# Flyback_SMPS.net
KiCad netlist of a schematic drawn in Altium Designer
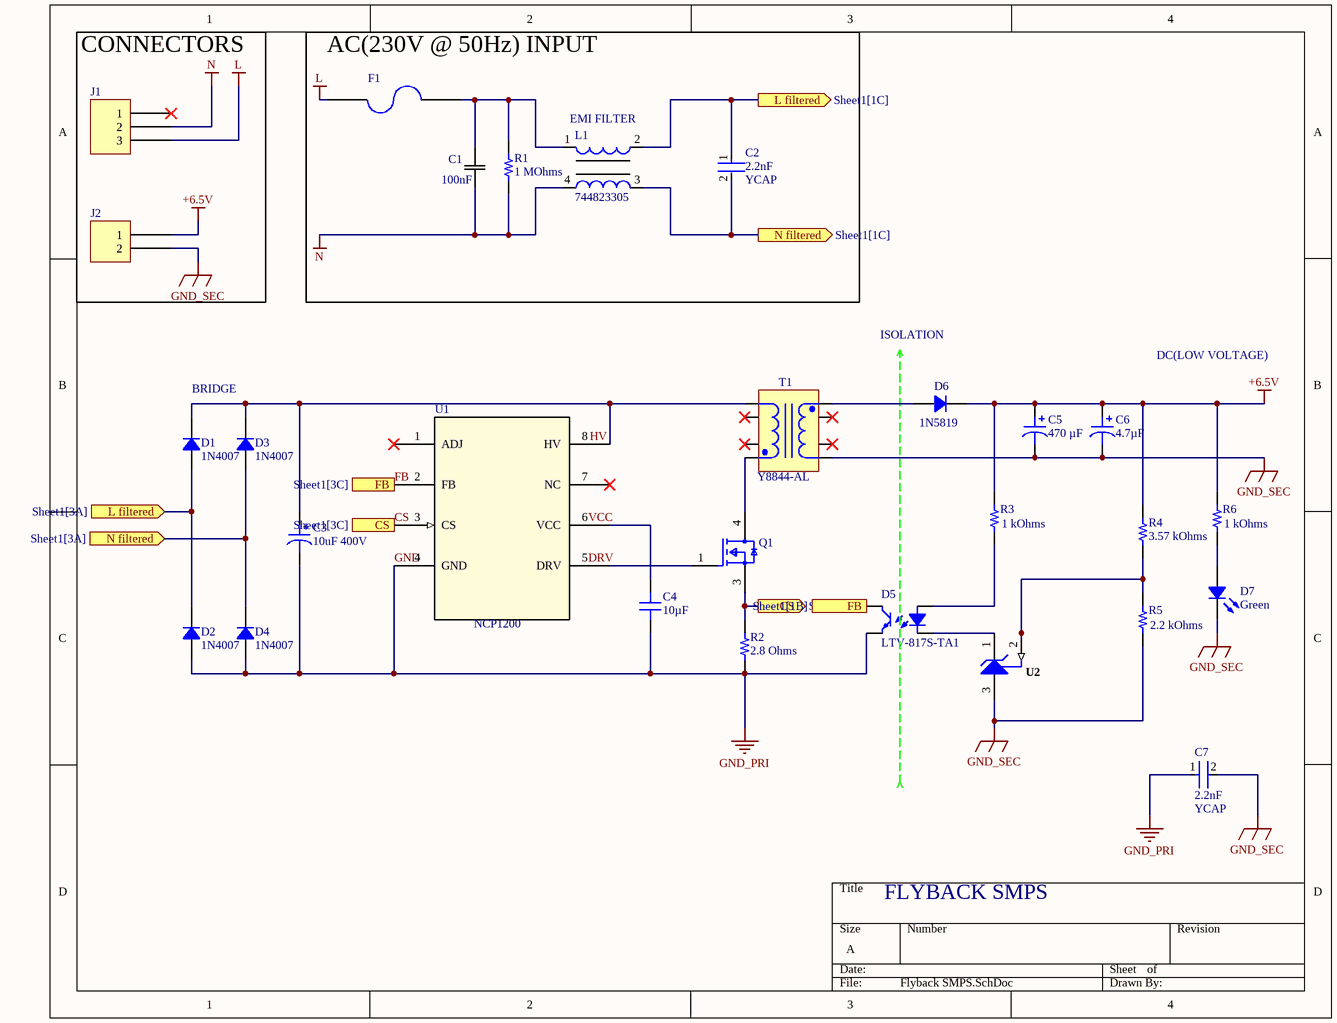
[diagram p0: Flyback SMPS.SchDoc]

(export (version "E")
  (design (tool "Eeschema 10.0.6"))
  (components
    (comp (ref "C1")
      (value "100nF")
      (footprint "CAP_B32652A--15--8.5x14.5x18_TDK")
      (description "No Description Available")
      (fields
        (field (name "MANUFACTURER_PART_NUMBER") "B32652A1103J000")
        (field (name "COPYRIGHT") "Copyright (C) 2025 Ultra Librarian. All rights reserved.")
      )
      (libsource (lib "transformer") (part "B32652A1103J000"))
    )
    (comp (ref "C2")
      (value "YCAP")
      (footprint "Vishay_0_MFG")
      (description "2200 pF ±20% 500VAC Ceramic Capacitor Y5V (F) Radial, Disc")
      (fields
        (field (name "TOLERANCE") "20%")
        (field (name "MANUFACTURER") "Vishay")
        (field (name "ALTIUM_VALUE") "2.2nF")
      )
      (libsource (lib "Tiberiu's Altium Workspace") (part "VY1222M37Y5VQ63V0"))
    )
    (comp (ref "C3")
      (value "10uF 400V")
      (footprint "CAP TH ALUM ELEC D10.00mm S5.00mm H17.50mm")
      (description "CAP 10 UF 20% 400 V")
      (fields (field (name "PART NUMBER") "860241375002") (field (name "MANUFACTURER") "Würth Elektronik"))
      (libsource (lib "Celestial Altium Library - altium_library") (part "Polarised Capacitor"))
    )
    (comp (ref "C4")
      (value "10µF")
      (footprint "CAP 1206_3216 - 1.8MM")
      (description "CAP CER 10UF 50V X5R 1206")
      (fields
        (field (name "PART NUMBER") "12065D106KAT2A")
        (field (name "CAPACITANCE") "10µF")
        (field (name "MANUFACTURER") "AVX Corporation")
      )
      (libsource (lib "Celestial Altium Library - altium_library") (part "Capacitor"))
    )
    (comp (ref "C5")
      (value "470 µF")
      (footprint "CAP AL TH D8 L3.5 H12.5")
      (description "CAP ALUM 470UF 20% 16V RADIAL")
      (fields (field (name "PART NUMBER") "UKW1C471MPD1TD") (field (name "MANUFACTURER") "Nichicon"))
      (libsource (lib "Celestial Altium Library - altium_library") (part "Polarised Capacitor"))
    )
    (comp (ref "C6")
      (value "4.7µF")
      (footprint "CAP TH ALUM ELEC D4.00mm S1.50mm H6.00mm")
      (description "CAP ALUM 4.7UF 20% 16V RADIAL")
      (fields (field (name "PART NUMBER") "UMP1C4R7MDD1TP") (field (name "MANUFACTURER") "Nichicon"))
      (libsource (lib "Celestial Altium Library - altium_library") (part "Polarised Capacitor"))
    )
    (comp (ref "C7")
      (value "YCAP")
      (footprint "Vishay_0_MFG")
      (description "2200 pF ±20% 500VAC Ceramic Capacitor Y5V (F) Radial, Disc")
      (fields
        (field (name "TOLERANCE") "20%")
        (field (name "MANUFACTURER") "Vishay")
        (field (name "ALTIUM_VALUE") "2.2nF")
      )
      (libsource (lib "Tiberiu's Altium Workspace") (part "VY1222M37Y5VQ63V0"))
    )
    (comp (ref "D1")
      (value "1N4007")
      (footprint "SOD123F")
      (description "STANDARD RECTIFIER 1000V SOD-123")
      (fields (field (name "PART NUMBER") "1N4007FLTR") (field (name "MANUFACTURER") "SMC Diode Solutions"))
      (libsource (lib "Celestial Altium Library - altium_library") (part "Diode"))
    )
    (comp (ref "D2")
      (value "1N4007")
      (footprint "SOD123F")
      (description "STANDARD RECTIFIER 1000V SOD-123")
      (fields (field (name "PART NUMBER") "1N4007FLTR") (field (name "MANUFACTURER") "SMC Diode Solutions"))
      (libsource (lib "Celestial Altium Library - altium_library") (part "Diode"))
    )
    (comp (ref "D3")
      (value "1N4007")
      (footprint "SOD123F")
      (description "STANDARD RECTIFIER 1000V SOD-123")
      (fields (field (name "PART NUMBER") "1N4007FLTR") (field (name "MANUFACTURER") "SMC Diode Solutions"))
      (libsource (lib "Celestial Altium Library - altium_library") (part "Diode"))
    )
    (comp (ref "D4")
      (value "1N4007")
      (footprint "SOD123F")
      (description "STANDARD RECTIFIER 1000V SOD-123")
      (fields (field (name "PART NUMBER") "1N4007FLTR") (field (name "MANUFACTURER") "SMC Diode Solutions"))
      (libsource (lib "Celestial Altium Library - altium_library") (part "Diode"))
    )
    (comp (ref "D5")
      (value "LTV-817S-TA1")
      (footprint "LITEON LTV-817")
      (description "OPTOISOLATR 5KV TRANSISTOR 4-SMD")
      (fields (field (name "MANUFACTURER") "Lite-On Inc."))
      (libsource (lib "Celestial Altium Library - altium_library") (part "Optoisolator"))
    )
    (comp (ref "D6")
      (value "1N5819")
      (footprint "SOD-123")
      (description "DIODE SCHOTTKY 40V 1A SOD123")
      (fields (field (name "PART NUMBER") "1N5819HW-7-F") (field (name "MANUFACTURER") "Diodes Incorporated"))
      (libsource (lib "Celestial Altium Library - altium_library") (part "Diode"))
    )
    (comp (ref "D7")
      (value "Green")
      (footprint "LED 0603_1608 GREEN")
      (description "NEXT GENERATION OF CHIP LED 0603")
      (fields
        (field (name "PART NUMBER") "LT Q99G.01-R2T1-25-1")
        (field (name "MANUFACTURER") "ams-OSRAM USA Inc.")
      )
      (libsource (lib "Celestial Altium Library - altium_library") (part "LED"))
    )
    (comp (ref "F1")
      (value "0679H2000-05")
      (footprint "FUSE 2410_6125 2")
      (description "FUSE BOARD MNT 2A 350VAC 72VDC")
      (fields (field (name "MANUFACTURER") "Bel Fuse Inc."))
      (libsource (lib "Celestial Altium Library - altium_library") (part "FUSE 0679H3500-05"))
    )
    (comp (ref "J1")
      (value "Part Number")
      (footprint "TE 282834-3")
      (description "TERM BLK 3P SIDE ENT 2.54MM PCB")
      (fields
        (field (name "PART NUMBER") "282834-3")
        (field (name "MANUFACTURER") "TE Connectivity AMP Connectors")
      )
      (libsource (lib "Celestial Altium Library - altium_library") (part "3 Pin"))
    )
    (comp (ref "J2")
      (value "282837-2")
      (footprint "TE 282837-2")
      (description "TERM BLK 2P SIDE ENT 5.08MM PCB")
      (fields (field (name "MANUFACTURER") "TE Connectivity AMP Connectors") (field (name "VOLTAGE") "300 V"))
      (libsource (lib "Celestial Altium Library - altium_library") (part "2 Pin"))
    )
    (comp (ref "L1")
      (value "744823305")
      (footprint "WE-CMB-M")
      (description "THT Common Mode Power Line Choke WE-CMB, L = 5.00 mH")
      (libsource (lib "transformer") (part "744823305"))
    )
    (comp (ref "Q1")
      (value "STD1NK60T4")
      (footprint "STMicroelectronics_DPAK_TO-252_-0068772_MFG")
      (description "N-Channel 600V 1A (Tc) 30W (Tc) Surface Mount DPAK")
      (fields
        (field (name "DIGIKEY PART NUMBER") "497-2483-1-ND")
        (field (name "MOUSER PART NUMBER") "511-STD1NK60")
      )
      (libsource (lib "Tiberiu's Altium Workspace") (part "STD1NK60T4"))
    )
    (comp (ref "R1")
      (value "1 MOhms")
      (footprint "RES 1210_3225")
      (description "RES 1M OHM 1% 3/4W 1210")
      (fields
        (field (name "PART NUMBER") "CRGP1210F1M0")
        (field (name "MANUFACTURER") "TE Connectivity Passive Product")
      )
      (libsource (lib "Celestial Altium Library - altium_library") (part "Resistor"))
    )
    (comp (ref "R2")
      (value "2.8 Ohms")
      (footprint "RES 1206_3216")
      (description "CPF 1206 2R8 0.1% 25PPM 1K RL")
      (fields
        (field (name "PART NUMBER") "CPF1206B2R8E1")
        (field (name "MANUFACTURER") "TE Connectivity Passive Product")
      )
      (libsource (lib "Celestial Altium Library - altium_library") (part "Resistor"))
    )
    (comp (ref "R3")
      (value "1 kOhms")
      (footprint "RES 0402_1005")
      (description "RES SMD 1K OHM 0.1% 1/16W 0402")
      (fields
        (field (name "PART NUMBER") "CPF0402B1K0E")
        (field (name "MANUFACTURER") "TE Connectivity Passive Product")
      )
      (libsource (lib "Celestial Altium Library - altium_library") (part "Resistor"))
    )
    (comp (ref "R4")
      (value "3.57 kOhms")
      (footprint "YAGEO RES 1206_3216")
      (description "RES 3.57K OHM 1% 1/16W 0402")
      (fields (field (name "PART NUMBER") "RC0402FR-073K57L") (field (name "MANUFACTURER") "Yageo"))
      (libsource (lib "Celestial Altium Library - altium_library") (part "Resistor"))
    )
    (comp (ref "R5")
      (value "2.2 kOhms")
      (footprint "RES 0402_1005")
      (description "RES SMD 2.2K OHM 0.5% 1/16W 0402")
      (fields (field (name "PART NUMBER") "RR0510P-222-D") (field (name "MANUFACTURER") "Susumu"))
      (libsource (lib "Celestial Altium Library - altium_library") (part "Resistor"))
    )
    (comp (ref "R6")
      (value "1 kOhms")
      (footprint "RES 0402_1005")
      (description "RES SMD 1K OHM 0.1% 1/16W 0402")
      (fields
        (field (name "PART NUMBER") "CPF0402B1K0E")
        (field (name "MANUFACTURER") "TE Connectivity Passive Product")
      )
      (libsource (lib "Celestial Altium Library - altium_library") (part "Resistor"))
    )
    (comp (ref "T1")
      (value "Y8844-AL")
      (footprint "COIL-Y8844-AL-8_V")
      (description "Flyback Transformer, 3.5 W, -40 to 85 degC, 18.3 x 20.1 x 14 mm Package")
      (fields (field (name "MANUFACTURER") "Coilcraft"))
      (libsource (lib "transformer") (part "Y8844-AL"))
    )
    (comp (ref "U1")
      (value "NCP1200")
      (footprint "SOIC8_ONS")
      (description "No Description Available")
      (fields
        (field (name "MANUFACTURER_PART_NUMBER") "NCP1200AD100R2")
        (field (name "COPYRIGHT") "Copyright (C) 2025 Ultra Librarian. All rights reserved.")
      )
      (libsource (lib "transformer") (part "NCP1200AD100R2"))
    )
    (comp (ref "U2")
      (value "TL431AQDBZRQ1")
      (footprint "DBZ0003A_L")
      (fields (field (name "MANUFACTURER") "Texas Instruments"))
      (libsource (lib "transformer") (part "TL431AQDBZRQ1"))
    )
  )
  (nets
    (net (code "1") (name "+6.5V") (class "Default")
      (node (ref "C5") (pin "1") (pinfunction "1_1") (pintype "passive"))
      (node (ref "C6") (pin "1") (pinfunction "1_1") (pintype "passive"))
      (node (ref "D6") (pin "2") (pinfunction "2_2") (pintype "passive"))
      (node (ref "J2") (pin "1") (pinfunction "1_1") (pintype "passive"))
      (node (ref "R3") (pin "2") (pinfunction "2_2") (pintype "passive"))
      (node (ref "R4") (pin "2") (pinfunction "2_2") (pintype "passive"))
      (node (ref "R6") (pin "2") (pinfunction "2_2") (pintype "passive"))
    )
    (net (code "2") (name "/CS") (class "Default")
      (node (ref "Q1") (pin "3") (pinfunction "S_3") (pintype "passive"))
      (node (ref "R2") (pin "2") (pinfunction "2_2") (pintype "passive"))
      (node (ref "U1") (pin "3") (pinfunction "CS_3") (pintype "input"))
    )
    (net (code "4") (name "/FB") (class "Default")
      (node (ref "D5") (pin "4") (pinfunction "4_4") (pintype "passive"))
      (node (ref "U1") (pin "2") (pinfunction "FB_2") (pintype "passive"))
    )
    (net (code "6") (name "/L filtered") (class "Default")
      (node (ref "C2") (pin "1") (pinfunction "1_1") (pintype "passive"))
      (node (ref "D1") (pin "1") (pinfunction "1_1") (pintype "passive"))
      (node (ref "D2") (pin "2") (pinfunction "2_2") (pintype "passive"))
      (node (ref "L1") (pin "2") (pinfunction "2_2") (pintype "passive"))
    )
    (net (code "7") (name "/N filtered") (class "Default")
      (node (ref "C2") (pin "2") (pinfunction "2_2") (pintype "passive"))
      (node (ref "D3") (pin "1") (pinfunction "1_1") (pintype "passive"))
      (node (ref "D4") (pin "2") (pinfunction "2_2") (pintype "passive"))
      (node (ref "L1") (pin "3") (pinfunction "3_3") (pintype "passive"))
    )
    (net (code "9") (name "GND_PRI") (class "Default")
      (node (ref "C3") (pin "2") (pinfunction "2_2") (pintype "passive"))
      (node (ref "C4") (pin "2") (pinfunction "2_2") (pintype "passive"))
      (node (ref "C7") (pin "1") (pinfunction "1_1") (pintype "passive"))
      (node (ref "D2") (pin "1") (pinfunction "1_1") (pintype "passive"))
      (node (ref "D4") (pin "1") (pinfunction "1_1") (pintype "passive"))
      (node (ref "D5") (pin "3") (pinfunction "3_3") (pintype "passive"))
      (node (ref "R2") (pin "1") (pinfunction "1_1") (pintype "passive"))
      (node (ref "U1") (pin "4") (pinfunction "GND_4") (pintype "power_in"))
    )
    (net (code "10") (name "GND_SEC") (class "Default")
      (node (ref "C5") (pin "2") (pinfunction "2_2") (pintype "passive"))
      (node (ref "C6") (pin "2") (pinfunction "2_2") (pintype "passive"))
      (node (ref "C7") (pin "2") (pinfunction "2_2") (pintype "passive"))
      (node (ref "D7") (pin "2") (pinfunction "2_2") (pintype "passive"))
      (node (ref "J2") (pin "2") (pinfunction "2_2") (pintype "passive"))
      (node (ref "R5") (pin "1") (pinfunction "1_1") (pintype "passive"))
      (node (ref "T1") (pin "1") (pinfunction "1_1") (pintype "passive"))
      (node (ref "U2") (pin "3") (pinfunction "ANODE_3") (pintype "power_in"))
    )
    (net (code "11") (name "L") (class "Default")
      (node (ref "F1") (pin "1") (pinfunction "1_1") (pintype "passive"))
      (node (ref "J1") (pin "3") (pinfunction "3_3") (pintype "passive"))
    )
    (net (code "12") (name "N") (class "Default")
      (node (ref "C1") (pin "1") (pinfunction "1_1") (pintype "passive"))
      (node (ref "J1") (pin "2") (pinfunction "2_2") (pintype "passive"))
      (node (ref "L1") (pin "4") (pinfunction "4_4") (pintype "passive"))
      (node (ref "R1") (pin "1") (pinfunction "1_1") (pintype "passive"))
    )
    (net (code "13") (name "Net-(C1-Pad2)") (class "Default")
      (node (ref "C1") (pin "2") (pinfunction "2_2") (pintype "passive"))
      (node (ref "F1") (pin "2") (pinfunction "2_2") (pintype "passive"))
      (node (ref "L1") (pin "1") (pinfunction "1_1") (pintype "passive"))
      (node (ref "R1") (pin "2") (pinfunction "2_2") (pintype "passive"))
    )
    (net (code "14") (name "Net-(D5-Pad1)") (class "Default")
      (node (ref "D5") (pin "1") (pinfunction "1_1") (pintype "passive"))
      (node (ref "R3") (pin "1") (pinfunction "1_1") (pintype "passive"))
    )
    (net (code "15") (name "Net-(D6-Pad1)") (class "Default")
      (node (ref "D6") (pin "1") (pinfunction "1_1") (pintype "passive"))
      (node (ref "T1") (pin "4") (pinfunction "4_4") (pintype "passive"))
    )
    (net (code "16") (name "Net-(D7-Pad1)") (class "Default")
      (node (ref "D7") (pin "1") (pinfunction "1_1") (pintype "passive"))
      (node (ref "R6") (pin "1") (pinfunction "1_1") (pintype "passive"))
    )
    (net (code "17") (name "Net-(Q1-D)") (class "Default")
      (node (ref "Q1") (pin "4") (pinfunction "D_4") (pintype "passive"))
      (node (ref "T1") (pin "5") (pinfunction "5_5") (pintype "passive"))
    )
    (net (code "18") (name "Net-(Q1-G)") (class "Default")
      (node (ref "Q1") (pin "1") (pinfunction "G_1") (pintype "passive"))
      (node (ref "U1") (pin "5") (pinfunction "DRV_5") (pintype "passive"))
    )
    (net (code "19") (name "Net-(U1-HV)") (class "Default")
      (node (ref "C3") (pin "1") (pinfunction "1_1") (pintype "passive"))
      (node (ref "D1") (pin "2") (pinfunction "2_2") (pintype "passive"))
      (node (ref "D3") (pin "2") (pinfunction "2_2") (pintype "passive"))
      (node (ref "T1") (pin "8") (pinfunction "8_8") (pintype "passive"))
      (node (ref "U1") (pin "8") (pinfunction "HV_8") (pintype "passive"))
    )
    (net (code "20") (name "Net-(U1-VCC)") (class "Default")
      (node (ref "C4") (pin "1") (pinfunction "1_1") (pintype "passive"))
      (node (ref "U1") (pin "6") (pinfunction "VCC_6") (pintype "power_in"))
    )
    (net (code "21") (name "Net-(U2-CATHODE)") (class "Default")
      (node (ref "D5") (pin "2") (pinfunction "2_2") (pintype "passive"))
      (node (ref "U2") (pin "1") (pinfunction "CATHODE_1") (pintype "passive"))
    )
    (net (code "22") (name "Net-(U2-REF)") (class "Default")
      (node (ref "R4") (pin "1") (pinfunction "1_1") (pintype "passive"))
      (node (ref "R5") (pin "2") (pinfunction "2_2") (pintype "passive"))
      (node (ref "U2") (pin "2") (pinfunction "REF_2") (pintype "input"))
    )
    (net (code "23") (name "unconnected-(J1-Pad1)") (class "Default")
      (node (ref "J1") (pin "1") (pinfunction "1_1") (pintype "passive+no_connect"))
    )
    (net (code "24") (name "unconnected-(T1-Pad2)") (class "Default")
      (node (ref "T1") (pin "2") (pinfunction "2_2") (pintype "passive+no_connect"))
    )
    (net (code "25") (name "unconnected-(T1-Pad3)") (class "Default")
      (node (ref "T1") (pin "3") (pinfunction "3_3") (pintype "passive+no_connect"))
    )
    (net (code "26") (name "unconnected-(T1-Pad6)") (class "Default")
      (node (ref "T1") (pin "6") (pinfunction "6_6") (pintype "passive+no_connect"))
    )
    (net (code "27") (name "unconnected-(T1-Pad7)") (class "Default")
      (node (ref "T1") (pin "7") (pinfunction "7_7") (pintype "passive+no_connect"))
    )
    (net (code "28") (name "unconnected-(U1-ADJ-Pad1)") (class "Default")
      (node (ref "U1") (pin "1") (pinfunction "ADJ_1") (pintype "passive+no_connect"))
    )
    (net (code "29") (name "unconnected-(U1-NC-Pad7)") (class "Default")
      (node (ref "U1") (pin "7") (pinfunction "NC_7") (pintype "passive+no_connect"))
    )
  )
)
